# io_connectors.net
KiCad netlist of a schematic drawn in Altium Designer
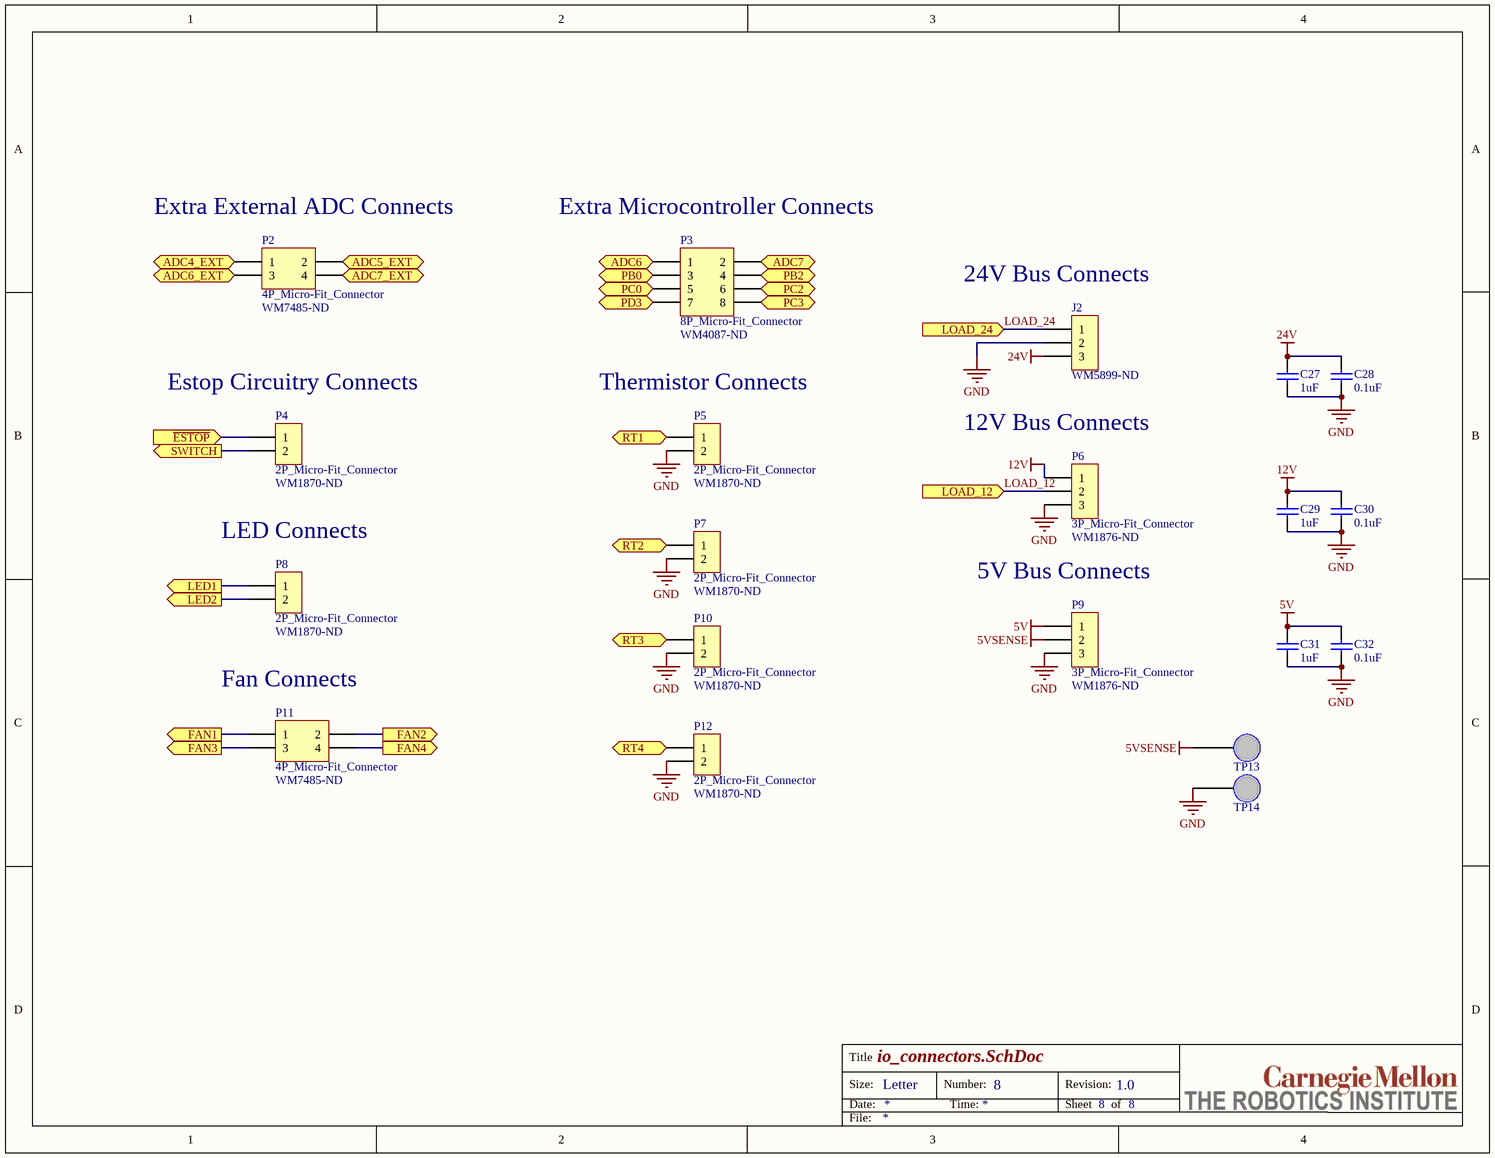
[diagram p0: io_connectors.SchDoc]

(export (version "E")
  (design (tool "Eeschema 10.0.6"))
  (components
    (comp (ref "C27")
      (value "1uF")
      (footprint "CAPC1608N")
      (description "Capacitor")
      (fields
        (field (name "MANUFACTURER") "Murata Electronics North America")
        (field (name "MANUFACTURER PART NUMBER") "GRM188R61H105KAALD")
        (field (name "PUBLISHER") "Altium Limited")
      )
      (libsource (lib "Miscellaneous Devices") (part "Cap"))
    )
    (comp (ref "C28")
      (value "0.1uF")
      (footprint "CAPC1608N")
      (description "Capacitor")
      (fields
        (field (name "MANUFACTURER") "Murata Electronics North America")
        (field (name "MANUFACTURER PART NUMBER") "GRM188R71H104JA93D")
        (field (name "PUBLISHER") "Altium Limited")
      )
      (libsource (lib "Miscellaneous Devices") (part "Cap"))
    )
    (comp (ref "C29")
      (value "1uF")
      (footprint "CAPC1608N")
      (description "Capacitor")
      (fields
        (field (name "MANUFACTURER") "Murata Electronics North America")
        (field (name "MANUFACTURER PART NUMBER") "GRM188R61H105KAALD")
        (field (name "PUBLISHER") "Altium Limited")
      )
      (libsource (lib "Miscellaneous Devices") (part "Cap"))
    )
    (comp (ref "C30")
      (value "0.1uF")
      (footprint "CAPC1608N")
      (description "Capacitor")
      (fields
        (field (name "MANUFACTURER") "Murata Electronics North America")
        (field (name "MANUFACTURER PART NUMBER") "GRM188R71H104JA93D")
        (field (name "PUBLISHER") "Altium Limited")
      )
      (libsource (lib "Miscellaneous Devices") (part "Cap"))
    )
    (comp (ref "C31")
      (value "1uF")
      (footprint "CAPC1608N")
      (description "Capacitor")
      (fields
        (field (name "MANUFACTURER") "Murata Electronics North America")
        (field (name "MANUFACTURER PART NUMBER") "GRM188R61H105KAALD")
        (field (name "PUBLISHER") "Altium Limited")
      )
      (libsource (lib "Miscellaneous Devices") (part "Cap"))
    )
    (comp (ref "C32")
      (value "0.1uF")
      (footprint "CAPC1608N")
      (description "Capacitor")
      (fields
        (field (name "MANUFACTURER") "Murata Electronics North America")
        (field (name "MANUFACTURER PART NUMBER") "GRM188R71H104JA93D")
        (field (name "PUBLISHER") "Altium Limited")
      )
      (libsource (lib "Miscellaneous Devices") (part "Cap"))
    )
    (comp (ref "J2")
      (value "Terminal Block")
      (footprint "3P_Molex_Terminal_Block")
      (description "Screw Terminal Block")
      (fields (field (name "SUPPLIER PART NUMBER 1") "WM5899-ND"))
      (libsource (lib "common") (part "3P_Molex_Beau_38660"))
    )
    (comp (ref "P2")
      (value "4P_Micro-Fit_Connector")
      (footprint "4P_Micro-Fit_Header")
      (description "4 Pin Microfit Connector")
      (fields (field (name "SUPPLIER PART NUMBER 1") "WM7485-ND") (field (name "PUBLISHER") "Altium Limited"))
      (libsource (lib "Molex_Micro_Fit_Connectors") (part "4P_Micro-Fit_Connector"))
    )
    (comp (ref "P3")
      (value "8P_Micro-Fit_Connector")
      (footprint "8P_Micro-Fit_Header")
      (description "8-Pin Microfit Connector")
      (fields (field (name "SUPPLIER PART NUMBER 1") "WM4087-ND") (field (name "PUBLISHER") "Altium Limited"))
      (libsource (lib "Molex_Micro_Fit_Connectors") (part "8P_Micro-Fit_Connector"))
    )
    (comp (ref "P4")
      (value "2P_Micro-Fit_Connector")
      (footprint "2P_Micro-Fit_Header")
      (description "2 Pin Microfit Connector")
      (fields
        (field (name "MANUFACTURER") "Molex, LLC")
        (field (name "MANUFACTURER PART NUMBER") "0436500203")
        (field (name "SUPPLIER PART NUMBER 1") "WM1870-ND")
      )
      (libsource (lib "Molex_Micro_Fit_Connectors") (part "2P_Micro-Fit_Connector"))
    )
    (comp (ref "P5")
      (value "2P_Micro-Fit_Connector")
      (footprint "2P_Micro-Fit_Header")
      (description "2 Pin Microfit Connector")
      (fields
        (field (name "MANUFACTURER") "Molex, LLC")
        (field (name "MANUFACTURER PART NUMBER") "0436500203")
        (field (name "SUPPLIER PART NUMBER 1") "WM1870-ND")
      )
      (libsource (lib "Molex_Micro_Fit_Connectors") (part "2P_Micro-Fit_Connector"))
    )
    (comp (ref "P6")
      (value "3P_Micro-Fit_Connector")
      (footprint "3P_Micro-Fit_Header")
      (description "3 Pin Microfit Connector")
      (fields
        (field (name "MANUFACTURER") "Molex, LLC")
        (field (name "MANUFACTURER PART NUMBER") "0436500304")
        (field (name "SUPPLIER PART NUMBER 1") "WM1876-ND")
      )
      (libsource (lib "Molex_Micro_Fit_Connectors") (part "3P_Micro-Fit_Connector"))
    )
    (comp (ref "P7")
      (value "2P_Micro-Fit_Connector")
      (footprint "2P_Micro-Fit_Header")
      (description "2 Pin Microfit Connector")
      (fields
        (field (name "MANUFACTURER") "Molex, LLC")
        (field (name "MANUFACTURER PART NUMBER") "0436500203")
        (field (name "SUPPLIER PART NUMBER 1") "WM1870-ND")
      )
      (libsource (lib "Molex_Micro_Fit_Connectors") (part "2P_Micro-Fit_Connector"))
    )
    (comp (ref "P8")
      (value "2P_Micro-Fit_Connector")
      (footprint "2P_Micro-Fit_Header")
      (description "2 Pin Microfit Connector")
      (fields
        (field (name "MANUFACTURER") "Molex, LLC")
        (field (name "MANUFACTURER PART NUMBER") "0436500203")
        (field (name "SUPPLIER PART NUMBER 1") "WM1870-ND")
      )
      (libsource (lib "Molex_Micro_Fit_Connectors") (part "2P_Micro-Fit_Connector"))
    )
    (comp (ref "P9")
      (value "3P_Micro-Fit_Connector")
      (footprint "3P_Micro-Fit_Header")
      (description "3 Pin Microfit Connector")
      (fields
        (field (name "MANUFACTURER") "Molex, LLC")
        (field (name "MANUFACTURER PART NUMBER") "0436500304")
        (field (name "SUPPLIER PART NUMBER 1") "WM1876-ND")
      )
      (libsource (lib "Molex_Micro_Fit_Connectors") (part "3P_Micro-Fit_Connector"))
    )
    (comp (ref "P10")
      (value "2P_Micro-Fit_Connector")
      (footprint "2P_Micro-Fit_Header")
      (description "2 Pin Microfit Connector")
      (fields
        (field (name "MANUFACTURER") "Molex, LLC")
        (field (name "MANUFACTURER PART NUMBER") "0436500203")
        (field (name "SUPPLIER PART NUMBER 1") "WM1870-ND")
      )
      (libsource (lib "Molex_Micro_Fit_Connectors") (part "2P_Micro-Fit_Connector"))
    )
    (comp (ref "P11")
      (value "4P_Micro-Fit_Connector")
      (footprint "4P_Micro-Fit_Header")
      (description "4 Pin Microfit Connector")
      (fields (field (name "SUPPLIER PART NUMBER 1") "WM7485-ND") (field (name "PUBLISHER") "Altium Limited"))
      (libsource (lib "Molex_Micro_Fit_Connectors") (part "4P_Micro-Fit_Connector"))
    )
    (comp (ref "P12")
      (value "2P_Micro-Fit_Connector")
      (footprint "2P_Micro-Fit_Header")
      (description "2 Pin Microfit Connector")
      (fields
        (field (name "MANUFACTURER") "Molex, LLC")
        (field (name "MANUFACTURER PART NUMBER") "0436500203")
        (field (name "SUPPLIER PART NUMBER 1") "WM1870-ND")
      )
      (libsource (lib "Molex_Micro_Fit_Connectors") (part "2P_Micro-Fit_Connector"))
    )
    (comp (ref "TP13")
      (value "5V")
      (footprint "TestPoint")
      (description "Test Point")
      (libsource (lib "common") (part "Ring_Terminal"))
    )
    (comp (ref "TP14")
      (value "GND")
      (footprint "TestPoint")
      (description "Test Point")
      (libsource (lib "common") (part "Ring_Terminal"))
    )
  )
  (nets
    (net (code "1") (name "/ADC4_EXT") (class "Default")
      (node (ref "P2") (pin "1") (pinfunction "1_1") (pintype "passive"))
    )
    (net (code "2") (name "/ADC5_EXT") (class "Default")
      (node (ref "P2") (pin "2") (pinfunction "2_2") (pintype "passive"))
    )
    (net (code "3") (name "/ADC6") (class "Default")
      (node (ref "P3") (pin "1") (pinfunction "1_1") (pintype "passive"))
    )
    (net (code "4") (name "/ADC6_EXT") (class "Default")
      (node (ref "P2") (pin "3") (pinfunction "3_3") (pintype "passive"))
    )
    (net (code "5") (name "/ADC7") (class "Default")
      (node (ref "P3") (pin "2") (pinfunction "2_2") (pintype "passive"))
    )
    (net (code "6") (name "/ADC7_EXT") (class "Default")
      (node (ref "P2") (pin "4") (pinfunction "4_4") (pintype "passive"))
    )
    (net (code "7") (name "/FAN1") (class "Default")
      (node (ref "P11") (pin "1") (pinfunction "1_1") (pintype "passive"))
    )
    (net (code "8") (name "/FAN2") (class "Default")
      (node (ref "P11") (pin "2") (pinfunction "2_2") (pintype "passive"))
    )
    (net (code "9") (name "/FAN3") (class "Default")
      (node (ref "P11") (pin "3") (pinfunction "3_3") (pintype "passive"))
    )
    (net (code "10") (name "/FAN4") (class "Default")
      (node (ref "P11") (pin "4") (pinfunction "4_4") (pintype "passive"))
    )
    (net (code "11") (name "/LED1") (class "Default")
      (node (ref "P8") (pin "1") (pinfunction "1_1") (pintype "passive"))
    )
    (net (code "12") (name "/LED2") (class "Default")
      (node (ref "P8") (pin "2") (pinfunction "2_2") (pintype "passive"))
    )
    (net (code "13") (name "/LOAD_12") (class "Default")
      (node (ref "P6") (pin "2") (pinfunction "2_2") (pintype "passive"))
    )
    (net (code "14") (name "/LOAD_24") (class "Default")
      (node (ref "J2") (pin "1") (pinfunction "1_1") (pintype "passive"))
    )
    (net (code "15") (name "/PB0") (class "Default")
      (node (ref "P3") (pin "3") (pinfunction "3_3") (pintype "passive"))
    )
    (net (code "16") (name "/PB2") (class "Default")
      (node (ref "P3") (pin "4") (pinfunction "4_4") (pintype "passive"))
    )
    (net (code "17") (name "/PC0") (class "Default")
      (node (ref "P3") (pin "5") (pinfunction "5_5") (pintype "passive"))
    )
    (net (code "18") (name "/PC2") (class "Default")
      (node (ref "P3") (pin "6") (pinfunction "6_6") (pintype "passive"))
    )
    (net (code "19") (name "/PC3") (class "Default")
      (node (ref "P3") (pin "8") (pinfunction "8_8") (pintype "passive"))
    )
    (net (code "20") (name "/PD3") (class "Default")
      (node (ref "P3") (pin "7") (pinfunction "7_7") (pintype "passive"))
    )
    (net (code "21") (name "/RT1") (class "Default")
      (node (ref "P5") (pin "1") (pinfunction "1_1") (pintype "passive"))
    )
    (net (code "22") (name "/RT2") (class "Default")
      (node (ref "P7") (pin "1") (pinfunction "1_1") (pintype "passive"))
    )
    (net (code "23") (name "/RT3") (class "Default")
      (node (ref "P10") (pin "1") (pinfunction "1_1") (pintype "passive"))
    )
    (net (code "24") (name "/RT4") (class "Default")
      (node (ref "P12") (pin "1") (pinfunction "1_1") (pintype "passive"))
    )
    (net (code "25") (name "/SWITCH") (class "Default")
      (node (ref "P4") (pin "2") (pinfunction "2_2") (pintype "passive"))
    )
    (net (code "26") (name "/~{ESTOP}") (class "Default")
      (node (ref "P4") (pin "1") (pinfunction "1_1") (pintype "passive"))
    )
    (net (code "27") (name "5V") (class "Default")
      (node (ref "C31") (pin "2") (pinfunction "2_2") (pintype "passive"))
      (node (ref "C32") (pin "2") (pinfunction "2_2") (pintype "passive"))
      (node (ref "P9") (pin "1") (pinfunction "1_1") (pintype "passive"))
    )
    (net (code "28") (name "5VSENSE") (class "Default")
      (node (ref "P9") (pin "2") (pinfunction "2_2") (pintype "passive"))
      (node (ref "TP13") (pin "1") (pinfunction "1_1") (pintype "passive"))
    )
    (net (code "29") (name "12V") (class "Default")
      (node (ref "C29") (pin "2") (pinfunction "2_2") (pintype "passive"))
      (node (ref "C30") (pin "2") (pinfunction "2_2") (pintype "passive"))
      (node (ref "P6") (pin "1") (pinfunction "1_1") (pintype "passive"))
    )
    (net (code "30") (name "24V") (class "Default")
      (node (ref "C27") (pin "2") (pinfunction "2_2") (pintype "passive"))
      (node (ref "C28") (pin "2") (pinfunction "2_2") (pintype "passive"))
      (node (ref "J2") (pin "3") (pinfunction "3_3") (pintype "passive"))
    )
    (net (code "31") (name "GND") (class "Default")
      (node (ref "C27") (pin "1") (pinfunction "1_1") (pintype "passive"))
      (node (ref "C28") (pin "1") (pinfunction "1_1") (pintype "passive"))
      (node (ref "C29") (pin "1") (pinfunction "1_1") (pintype "passive"))
      (node (ref "C30") (pin "1") (pinfunction "1_1") (pintype "passive"))
      (node (ref "C31") (pin "1") (pinfunction "1_1") (pintype "passive"))
      (node (ref "C32") (pin "1") (pinfunction "1_1") (pintype "passive"))
      (node (ref "J2") (pin "2") (pinfunction "2_2") (pintype "passive"))
      (node (ref "P10") (pin "2") (pinfunction "2_2") (pintype "passive"))
      (node (ref "P12") (pin "2") (pinfunction "2_2") (pintype "passive"))
      (node (ref "P5") (pin "2") (pinfunction "2_2") (pintype "passive"))
      (node (ref "P6") (pin "3") (pinfunction "3_3") (pintype "passive"))
      (node (ref "P7") (pin "2") (pinfunction "2_2") (pintype "passive"))
      (node (ref "P9") (pin "3") (pinfunction "3_3") (pintype "passive"))
      (node (ref "TP14") (pin "1") (pinfunction "1_1") (pintype "passive"))
    )
  )
)
